# gate_delay_v2_main.net
KiCad netlist of a schematic drawn in EAGLE
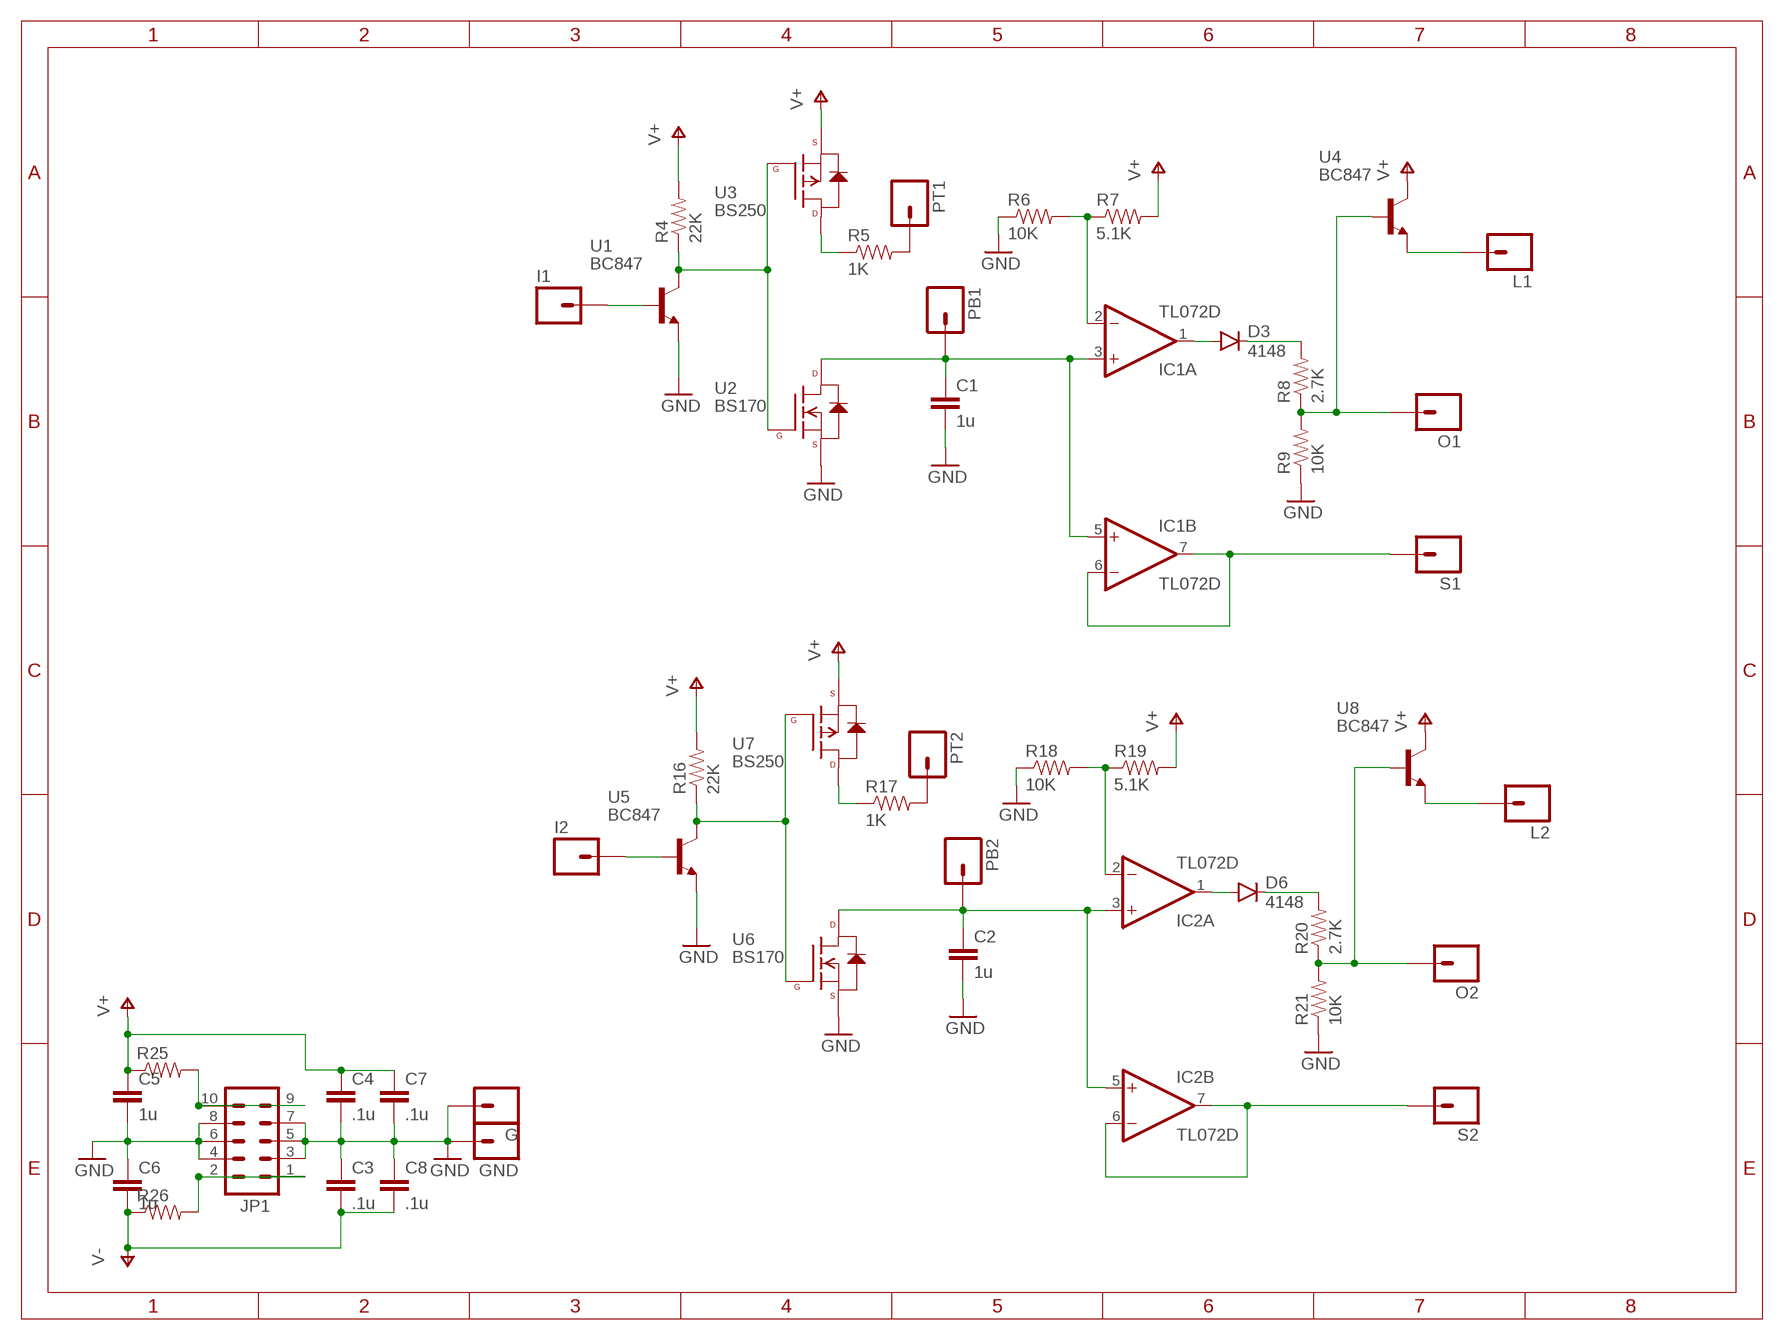
[diagram p0: schematic, sheet 1]

(export (version "E")
  (design (tool "Eeschema 10.0.6"))
  (components
    (comp (ref "C1")
      (value "1u")
      (footprint "eagle-import:1206")
      (libsource (lib "eagle-import") (part "CAP1206"))
    )
    (comp (ref "C2")
      (value "1u")
      (footprint "eagle-import:1206")
      (libsource (lib "eagle-import") (part "CAP1206"))
    )
    (comp (ref "C3")
      (value ".1u")
      (footprint "eagle-import:0805")
      (libsource (lib "eagle-import") (part "CAP0805"))
    )
    (comp (ref "C4")
      (value ".1u")
      (footprint "eagle-import:0805")
      (libsource (lib "eagle-import") (part "CAP0805"))
    )
    (comp (ref "C5")
      (value "1u")
      (footprint "eagle-import:1206")
      (libsource (lib "eagle-import") (part "CAP1206"))
    )
    (comp (ref "C6")
      (value "1u")
      (footprint "eagle-import:1206")
      (libsource (lib "eagle-import") (part "CAP1206"))
    )
    (comp (ref "C7")
      (value ".1u")
      (footprint "eagle-import:0805")
      (libsource (lib "eagle-import") (part "CAP0805"))
    )
    (comp (ref "C8")
      (value ".1u")
      (footprint "eagle-import:0805")
      (libsource (lib "eagle-import") (part "CAP0805"))
    )
    (comp (ref "D3")
      (value "4148")
      (footprint "eagle-import:SOD-123")
      (libsource (lib "eagle-import") (part "DIODESOD123"))
    )
    (comp (ref "D6")
      (value "4148")
      (footprint "eagle-import:SOD-123")
      (libsource (lib "eagle-import") (part "DIODESOD123"))
    )
    (comp (ref "G")
      (value "M01PTH")
      (footprint "eagle-import:1X01")
      (libsource (lib "eagle-import") (part "M01PTH"))
    )
    (comp (ref "GND")
      (value "M01PTH")
      (footprint "eagle-import:1X01")
      (libsource (lib "eagle-import") (part "M01PTH"))
    )
    (comp (ref "I1")
      (value "M01PTH")
      (footprint "eagle-import:1X01")
      (libsource (lib "eagle-import") (part "M01PTH"))
    )
    (comp (ref "I2")
      (value "M01PTH")
      (footprint "eagle-import:1X01")
      (libsource (lib "eagle-import") (part "M01PTH"))
    )
    (comp (ref "IC1")
      (value "TL072D")
      (footprint "eagle-import:SO08")
      (libsource (lib "eagle-import") (part "TL072D"))
    )
    (comp (ref "IC2")
      (value "TL072D")
      (footprint "eagle-import:SO08")
      (libsource (lib "eagle-import") (part "TL072D"))
    )
    (comp (ref "JP1")
      (value "M05X2PTH")
      (footprint "eagle-import:AVR_ICSP")
      (libsource (lib "eagle-import") (part "M05X2PTH"))
    )
    (comp (ref "L1")
      (value "M01PTH")
      (footprint "eagle-import:1X01")
      (libsource (lib "eagle-import") (part "M01PTH"))
    )
    (comp (ref "L2")
      (value "M01PTH")
      (footprint "eagle-import:1X01")
      (libsource (lib "eagle-import") (part "M01PTH"))
    )
    (comp (ref "O1")
      (value "M01PTH")
      (footprint "eagle-import:1X01")
      (libsource (lib "eagle-import") (part "M01PTH"))
    )
    (comp (ref "O2")
      (value "M01PTH")
      (footprint "eagle-import:1X01")
      (libsource (lib "eagle-import") (part "M01PTH"))
    )
    (comp (ref "PB1")
      (value "M01PTH")
      (footprint "eagle-import:1X01")
      (libsource (lib "eagle-import") (part "M01PTH"))
    )
    (comp (ref "PB2")
      (value "M01PTH")
      (footprint "eagle-import:1X01")
      (libsource (lib "eagle-import") (part "M01PTH"))
    )
    (comp (ref "PT1")
      (value "M01PTH")
      (footprint "eagle-import:1X01")
      (libsource (lib "eagle-import") (part "M01PTH"))
    )
    (comp (ref "PT2")
      (value "M01PTH")
      (footprint "eagle-import:1X01")
      (libsource (lib "eagle-import") (part "M01PTH"))
    )
    (comp (ref "R4")
      (value "22K")
      (footprint "eagle-import:0805@1")
      (libsource (lib "eagle-import") (part "RESISTOR0805-RES"))
    )
    (comp (ref "R5")
      (value "1K")
      (footprint "eagle-import:0805@1")
      (libsource (lib "eagle-import") (part "RESISTOR0805-RES"))
    )
    (comp (ref "R6")
      (value "10K")
      (footprint "eagle-import:0805@1")
      (libsource (lib "eagle-import") (part "RESISTOR0805-RES"))
    )
    (comp (ref "R7")
      (value "5.1K")
      (footprint "eagle-import:0805@1")
      (libsource (lib "eagle-import") (part "RESISTOR0805-RES"))
    )
    (comp (ref "R8")
      (value "2.7K")
      (footprint "eagle-import:0805@1")
      (libsource (lib "eagle-import") (part "RESISTOR0805-RES"))
    )
    (comp (ref "R9")
      (value "10K")
      (footprint "eagle-import:0805@1")
      (libsource (lib "eagle-import") (part "RESISTOR0805-RES"))
    )
    (comp (ref "R16")
      (value "22K")
      (footprint "eagle-import:0805@1")
      (libsource (lib "eagle-import") (part "RESISTOR0805-RES"))
    )
    (comp (ref "R17")
      (value "1K")
      (footprint "eagle-import:0805@1")
      (libsource (lib "eagle-import") (part "RESISTOR0805-RES"))
    )
    (comp (ref "R18")
      (value "10K")
      (footprint "eagle-import:0805@1")
      (libsource (lib "eagle-import") (part "RESISTOR0805-RES"))
    )
    (comp (ref "R19")
      (value "5.1K")
      (footprint "eagle-import:0805@1")
      (libsource (lib "eagle-import") (part "RESISTOR0805-RES"))
    )
    (comp (ref "R20")
      (value "2.7K")
      (footprint "eagle-import:0805@1")
      (libsource (lib "eagle-import") (part "RESISTOR0805-RES"))
    )
    (comp (ref "R21")
      (value "10K")
      (footprint "eagle-import:0805@1")
      (libsource (lib "eagle-import") (part "RESISTOR0805-RES"))
    )
    (comp (ref "R25")
      (value "RESISTOR0805-RES")
      (footprint "eagle-import:0805@1")
      (libsource (lib "eagle-import") (part "RESISTOR0805-RES"))
    )
    (comp (ref "R26")
      (value "RESISTOR0805-RES")
      (footprint "eagle-import:0805@1")
      (libsource (lib "eagle-import") (part "RESISTOR0805-RES"))
    )
    (comp (ref "S1")
      (value "M01PTH")
      (footprint "eagle-import:1X01")
      (libsource (lib "eagle-import") (part "M01PTH"))
    )
    (comp (ref "S2")
      (value "M01PTH")
      (footprint "eagle-import:1X01")
      (libsource (lib "eagle-import") (part "M01PTH"))
    )
    (comp (ref "U1")
      (value "BC847")
      (footprint "eagle-import:SOT23")
      (libsource (lib "eagle-import") (part "BC847"))
    )
    (comp (ref "U2")
      (value "BS170")
      (footprint "eagle-import:SOT23-3")
      (libsource (lib "eagle-import") (part "N-CHANNEL-MOSFET-BSS138"))
    )
    (comp (ref "U3")
      (value "BS250")
      (footprint "eagle-import:SOT23-3")
      (libsource (lib "eagle-import") (part "P-CHANNEL-MOSFET"))
    )
    (comp (ref "U4")
      (value "BC847")
      (footprint "eagle-import:SOT23")
      (libsource (lib "eagle-import") (part "BC847"))
    )
    (comp (ref "U5")
      (value "BC847")
      (footprint "eagle-import:SOT23")
      (libsource (lib "eagle-import") (part "BC847"))
    )
    (comp (ref "U6")
      (value "BS170")
      (footprint "eagle-import:SOT23-3")
      (libsource (lib "eagle-import") (part "N-CHANNEL-MOSFET-BSS138"))
    )
    (comp (ref "U7")
      (value "BS250")
      (footprint "eagle-import:SOT23-3")
      (libsource (lib "eagle-import") (part "P-CHANNEL-MOSFET"))
    )
    (comp (ref "U8")
      (value "BC847")
      (footprint "eagle-import:SOT23")
      (libsource (lib "eagle-import") (part "BC847"))
    )
  )
  (nets
    (net (code "1") (name "GND") (class "Default")
      (node (ref "C1") (pin "2") (pinfunction "2_2") (pintype "passive"))
      (node (ref "C2") (pin "2") (pinfunction "2_2") (pintype "passive"))
      (node (ref "C3") (pin "1") (pinfunction "1_1") (pintype "passive"))
      (node (ref "C4") (pin "2") (pinfunction "2_2") (pintype "passive"))
      (node (ref "C5") (pin "2") (pinfunction "2_2") (pintype "passive"))
      (node (ref "C6") (pin "1") (pinfunction "1_1") (pintype "passive"))
      (node (ref "C7") (pin "2") (pinfunction "2_2") (pintype "passive"))
      (node (ref "C8") (pin "1") (pinfunction "1_1") (pintype "passive"))
      (node (ref "G") (pin "1") (pinfunction "1_1") (pintype "passive"))
      (node (ref "GND") (pin "1") (pinfunction "1_1") (pintype "passive"))
      (node (ref "JP1") (pin "3") (pinfunction "3_3") (pintype "passive"))
      (node (ref "JP1") (pin "4") (pinfunction "4_4") (pintype "passive"))
      (node (ref "JP1") (pin "5") (pinfunction "5_5") (pintype "passive"))
      (node (ref "JP1") (pin "6") (pinfunction "6_6") (pintype "passive"))
      (node (ref "JP1") (pin "7") (pinfunction "7_7") (pintype "passive"))
      (node (ref "JP1") (pin "8") (pinfunction "8_8") (pintype "passive"))
      (node (ref "R18") (pin "1") (pinfunction "1_1") (pintype "passive"))
      (node (ref "R21") (pin "1") (pinfunction "1_1") (pintype "passive"))
      (node (ref "R6") (pin "1") (pinfunction "1_1") (pintype "passive"))
      (node (ref "R9") (pin "1") (pinfunction "1_1") (pintype "passive"))
      (node (ref "U1") (pin "2") (pinfunction "E_2") (pintype "passive"))
      (node (ref "U2") (pin "2") (pinfunction "S_2") (pintype "passive"))
      (node (ref "U5") (pin "2") (pinfunction "E_2") (pintype "passive"))
      (node (ref "U6") (pin "2") (pinfunction "S_2") (pintype "passive"))
    )
    (net (code "2") (name "Net-(D3-PadC)") (class "Default")
      (node (ref "D3") (pin "C") (pinfunction "C_C") (pintype "passive"))
      (node (ref "R8") (pin "2") (pinfunction "2_2") (pintype "passive"))
    )
    (net (code "3") (name "Net-(D6-PadC)") (class "Default")
      (node (ref "D6") (pin "C") (pinfunction "C_C") (pintype "passive"))
      (node (ref "R20") (pin "2") (pinfunction "2_2") (pintype "passive"))
    )
    (net (code "4") (name "Net-(IC1A-+IN)") (class "Default")
      (node (ref "C1") (pin "1") (pinfunction "1_1") (pintype "passive"))
      (node (ref "IC1") (pin "3") (pinfunction "+IN_3") (pintype "input"))
      (node (ref "IC1") (pin "5") (pinfunction "+IN_5") (pintype "input"))
      (node (ref "PB1") (pin "1") (pinfunction "1_1") (pintype "passive"))
      (node (ref "U2") (pin "3") (pinfunction "D_3") (pintype "passive"))
    )
    (net (code "5") (name "Net-(IC1A--IN)") (class "Default")
      (node (ref "IC1") (pin "2") (pinfunction "-IN_2") (pintype "input"))
      (node (ref "R6") (pin "2") (pinfunction "2_2") (pintype "passive"))
      (node (ref "R7") (pin "1") (pinfunction "1_1") (pintype "passive"))
    )
    (net (code "6") (name "Net-(IC1A-OUT)") (class "Default")
      (node (ref "D3") (pin "A") (pinfunction "A_A") (pintype "passive"))
      (node (ref "IC1") (pin "1") (pinfunction "OUT_1") (pintype "output"))
    )
    (net (code "7") (name "Net-(IC1B--IN)") (class "Default")
      (node (ref "IC1") (pin "6") (pinfunction "-IN_6") (pintype "input"))
      (node (ref "IC1") (pin "7") (pinfunction "OUT_7") (pintype "output"))
      (node (ref "S1") (pin "1") (pinfunction "1_1") (pintype "passive"))
    )
    (net (code "8") (name "Net-(IC2A-+IN)") (class "Default")
      (node (ref "C2") (pin "1") (pinfunction "1_1") (pintype "passive"))
      (node (ref "IC2") (pin "3") (pinfunction "+IN_3") (pintype "input"))
      (node (ref "IC2") (pin "5") (pinfunction "+IN_5") (pintype "input"))
      (node (ref "PB2") (pin "1") (pinfunction "1_1") (pintype "passive"))
      (node (ref "U6") (pin "3") (pinfunction "D_3") (pintype "passive"))
    )
    (net (code "9") (name "Net-(IC2A--IN)") (class "Default")
      (node (ref "IC2") (pin "2") (pinfunction "-IN_2") (pintype "input"))
      (node (ref "R18") (pin "2") (pinfunction "2_2") (pintype "passive"))
      (node (ref "R19") (pin "1") (pinfunction "1_1") (pintype "passive"))
    )
    (net (code "10") (name "Net-(IC2A-OUT)") (class "Default")
      (node (ref "D6") (pin "A") (pinfunction "A_A") (pintype "passive"))
      (node (ref "IC2") (pin "1") (pinfunction "OUT_1") (pintype "output"))
    )
    (net (code "11") (name "Net-(IC2B--IN)") (class "Default")
      (node (ref "IC2") (pin "6") (pinfunction "-IN_6") (pintype "input"))
      (node (ref "IC2") (pin "7") (pinfunction "OUT_7") (pintype "output"))
      (node (ref "S2") (pin "1") (pinfunction "1_1") (pintype "passive"))
    )
    (net (code "12") (name "Net-(JP1-Pad1)") (class "Default")
      (node (ref "JP1") (pin "1") (pinfunction "1_1") (pintype "passive"))
      (node (ref "JP1") (pin "2") (pinfunction "2_2") (pintype "passive"))
      (node (ref "R26") (pin "2") (pinfunction "2_2") (pintype "passive"))
    )
    (net (code "13") (name "Net-(JP1-Pad10)") (class "Default")
      (node (ref "JP1") (pin "10") (pinfunction "10_10") (pintype "passive"))
      (node (ref "JP1") (pin "9") (pinfunction "9_9") (pintype "passive"))
      (node (ref "R25") (pin "2") (pinfunction "2_2") (pintype "passive"))
    )
    (net (code "14") (name "Net-(PT1-Pad1)") (class "Default")
      (node (ref "PT1") (pin "1") (pinfunction "1_1") (pintype "passive"))
      (node (ref "R5") (pin "2") (pinfunction "2_2") (pintype "passive"))
    )
    (net (code "15") (name "Net-(PT2-Pad1)") (class "Default")
      (node (ref "PT2") (pin "1") (pinfunction "1_1") (pintype "passive"))
      (node (ref "R17") (pin "2") (pinfunction "2_2") (pintype "passive"))
    )
    (net (code "16") (name "Net-(U1-B)") (class "Default")
      (node (ref "I1") (pin "1") (pinfunction "1_1") (pintype "passive"))
      (node (ref "U1") (pin "1") (pinfunction "B_1") (pintype "passive"))
    )
    (net (code "17") (name "Net-(U1-C)") (class "Default")
      (node (ref "R4") (pin "1") (pinfunction "1_1") (pintype "passive"))
      (node (ref "U1") (pin "3") (pinfunction "C_3") (pintype "passive"))
      (node (ref "U2") (pin "1") (pinfunction "G_1") (pintype "passive"))
      (node (ref "U3") (pin "1") (pinfunction "G_1") (pintype "passive"))
    )
    (net (code "18") (name "Net-(U3-D)") (class "Default")
      (node (ref "R5") (pin "1") (pinfunction "1_1") (pintype "passive"))
      (node (ref "U3") (pin "3") (pinfunction "D_3") (pintype "passive"))
    )
    (net (code "19") (name "Net-(U4-B)") (class "Default")
      (node (ref "O1") (pin "1") (pinfunction "1_1") (pintype "passive"))
      (node (ref "R8") (pin "1") (pinfunction "1_1") (pintype "passive"))
      (node (ref "R9") (pin "2") (pinfunction "2_2") (pintype "passive"))
      (node (ref "U4") (pin "1") (pinfunction "B_1") (pintype "passive"))
    )
    (net (code "20") (name "Net-(U4-E)") (class "Default")
      (node (ref "L1") (pin "1") (pinfunction "1_1") (pintype "passive"))
      (node (ref "U4") (pin "2") (pinfunction "E_2") (pintype "passive"))
    )
    (net (code "21") (name "Net-(U5-B)") (class "Default")
      (node (ref "I2") (pin "1") (pinfunction "1_1") (pintype "passive"))
      (node (ref "U5") (pin "1") (pinfunction "B_1") (pintype "passive"))
    )
    (net (code "22") (name "Net-(U5-C)") (class "Default")
      (node (ref "R16") (pin "1") (pinfunction "1_1") (pintype "passive"))
      (node (ref "U5") (pin "3") (pinfunction "C_3") (pintype "passive"))
      (node (ref "U6") (pin "1") (pinfunction "G_1") (pintype "passive"))
      (node (ref "U7") (pin "1") (pinfunction "G_1") (pintype "passive"))
    )
    (net (code "23") (name "Net-(U7-D)") (class "Default")
      (node (ref "R17") (pin "1") (pinfunction "1_1") (pintype "passive"))
      (node (ref "U7") (pin "3") (pinfunction "D_3") (pintype "passive"))
    )
    (net (code "24") (name "Net-(U8-B)") (class "Default")
      (node (ref "O2") (pin "1") (pinfunction "1_1") (pintype "passive"))
      (node (ref "R20") (pin "1") (pinfunction "1_1") (pintype "passive"))
      (node (ref "R21") (pin "2") (pinfunction "2_2") (pintype "passive"))
      (node (ref "U8") (pin "1") (pinfunction "B_1") (pintype "passive"))
    )
    (net (code "25") (name "Net-(U8-E)") (class "Default")
      (node (ref "L2") (pin "1") (pinfunction "1_1") (pintype "passive"))
      (node (ref "U8") (pin "2") (pinfunction "E_2") (pintype "passive"))
    )
    (net (code "26") (name "V+") (class "Default")
      (node (ref "C4") (pin "1") (pinfunction "1_1") (pintype "passive"))
      (node (ref "C5") (pin "1") (pinfunction "1_1") (pintype "passive"))
      (node (ref "C7") (pin "1") (pinfunction "1_1") (pintype "passive"))
      (node (ref "R16") (pin "2") (pinfunction "2_2") (pintype "passive"))
      (node (ref "R19") (pin "2") (pinfunction "2_2") (pintype "passive"))
      (node (ref "R25") (pin "1") (pinfunction "1_1") (pintype "passive"))
      (node (ref "R4") (pin "2") (pinfunction "2_2") (pintype "passive"))
      (node (ref "R7") (pin "2") (pinfunction "2_2") (pintype "passive"))
      (node (ref "U3") (pin "2") (pinfunction "S_2") (pintype "passive"))
      (node (ref "U4") (pin "3") (pinfunction "C_3") (pintype "passive"))
      (node (ref "U7") (pin "2") (pinfunction "S_2") (pintype "passive"))
      (node (ref "U8") (pin "3") (pinfunction "C_3") (pintype "passive"))
    )
    (net (code "27") (name "V-") (class "Default")
      (node (ref "C3") (pin "2") (pinfunction "2_2") (pintype "passive"))
      (node (ref "C6") (pin "2") (pinfunction "2_2") (pintype "passive"))
      (node (ref "C8") (pin "2") (pinfunction "2_2") (pintype "passive"))
      (node (ref "R26") (pin "1") (pinfunction "1_1") (pintype "passive"))
    )
  )
)
